# midi_thru.net
KiCad netlist of a schematic drawn in EAGLE
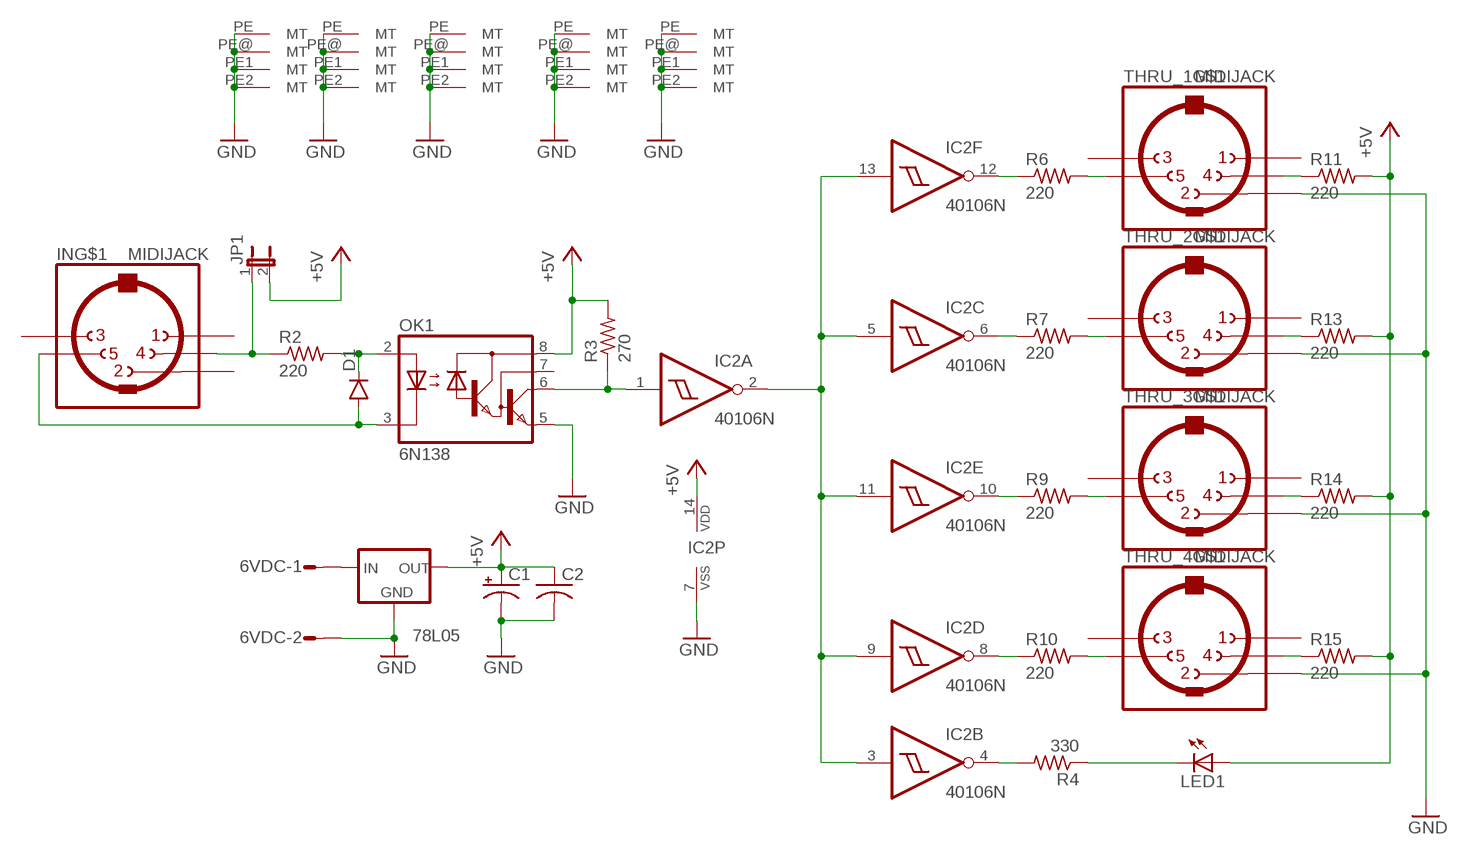
[diagram p0: schematic, sheet 1]

(export (version "E")
  (design (tool "Eeschema 10.0.6"))
  (components
    (comp (ref "6VDC")
      (value "S02P")
      (footprint "eagle-import:S02P")
      (libsource (lib "eagle-import") (part "S02P"))
    )
    (comp (ref "78L05")
      (value "79LXX")
      (footprint "eagle-import:79LXX")
      (libsource (lib "eagle-import") (part "79LXX"))
    )
    (comp (ref "C1")
      (value "CPOL-USB45181A")
      (footprint "eagle-import:B45181A")
      (libsource (lib "eagle-import") (part "CPOL-USB45181A"))
    )
    (comp (ref "C2")
      (value "C-US025-024X044")
      (footprint "eagle-import:C025-024X044")
      (libsource (lib "eagle-import") (part "C-US025-024X044"))
    )
    (comp (ref "D1")
      (value "DIODE1N4148")
      (footprint "eagle-import:DIODE-1N4148")
      (libsource (lib "eagle-import") (part "DIODE1N4148"))
    )
    (comp (ref "IC2")
      (value "40106N")
      (footprint "eagle-import:DIL14")
      (libsource (lib "eagle-import") (part "40106N"))
    )
    (comp (ref "IN")
      (value "MIDIJACK")
      (footprint "eagle-import:CP-2350")
      (libsource (lib "eagle-import") (part "MIDIJACK"))
    )
    (comp (ref "JP1")
      (value "JP1E")
      (footprint "eagle-import:JP1")
      (libsource (lib "eagle-import") (part "JP1E"))
    )
    (comp (ref "LED1")
      (value "LED5MM")
      (footprint "eagle-import:LED5MM")
      (libsource (lib "eagle-import") (part "LED5MM"))
    )
    (comp (ref "OK1")
      (value "6N138")
      (footprint "eagle-import:DIL08")
      (fields (field (name "MF") "VISHAY/TELEFUNKEN"))
      (libsource (lib "eagle-import") (part "6N138"))
    )
    (comp (ref "R2")
      (value "220")
      (footprint "eagle-import:0207_7")
      (libsource (lib "eagle-import") (part "R-US_0207/7"))
    )
    (comp (ref "R3")
      (value "270")
      (footprint "eagle-import:0207_7")
      (libsource (lib "eagle-import") (part "R-US_0207/7"))
    )
    (comp (ref "R4")
      (value "330")
      (footprint "eagle-import:0207_7")
      (libsource (lib "eagle-import") (part "R-US_0207/7"))
    )
    (comp (ref "R6")
      (value "220")
      (footprint "eagle-import:0207_7")
      (libsource (lib "eagle-import") (part "R-US_0207/7"))
    )
    (comp (ref "R7")
      (value "220")
      (footprint "eagle-import:0207_7")
      (libsource (lib "eagle-import") (part "R-US_0207/7"))
    )
    (comp (ref "R9")
      (value "220")
      (footprint "eagle-import:0207_7")
      (libsource (lib "eagle-import") (part "R-US_0207/7"))
    )
    (comp (ref "R10")
      (value "220")
      (footprint "eagle-import:0207_7")
      (libsource (lib "eagle-import") (part "R-US_0207/7"))
    )
    (comp (ref "R11")
      (value "220")
      (footprint "eagle-import:0207_7")
      (libsource (lib "eagle-import") (part "R-US_0207/7"))
    )
    (comp (ref "R13")
      (value "220")
      (footprint "eagle-import:0207_7")
      (libsource (lib "eagle-import") (part "R-US_0207/7"))
    )
    (comp (ref "R14")
      (value "220")
      (footprint "eagle-import:0207_7")
      (libsource (lib "eagle-import") (part "R-US_0207/7"))
    )
    (comp (ref "R15")
      (value "220")
      (footprint "eagle-import:0207_7")
      (libsource (lib "eagle-import") (part "R-US_0207/7"))
    )
    (comp (ref "THRU_1")
      (value "MIDIJACK")
      (footprint "eagle-import:CP-2350")
      (libsource (lib "eagle-import") (part "MIDIJACK"))
    )
    (comp (ref "THRU_2")
      (value "MIDIJACK")
      (footprint "eagle-import:CP-2350")
      (libsource (lib "eagle-import") (part "MIDIJACK"))
    )
    (comp (ref "THRU_3")
      (value "MIDIJACK")
      (footprint "eagle-import:CP-2350")
      (libsource (lib "eagle-import") (part "MIDIJACK"))
    )
    (comp (ref "THRU_4")
      (value "MIDIJACK")
      (footprint "eagle-import:CP-2350")
      (libsource (lib "eagle-import") (part "MIDIJACK"))
    )
  )
  (nets
    (net (code "1") (name "+5V") (class "Default")
      (node (ref "78L05") (pin "OUT") (pinfunction "OUT_OUT") (pintype "passive"))
      (node (ref "C1") (pin "+") (pinfunction "+_+") (pintype "passive"))
      (node (ref "C2") (pin "1") (pinfunction "1_1") (pintype "passive"))
      (node (ref "IC2") (pin "14") (pinfunction "VDD_14") (pintype "power_in"))
      (node (ref "JP1") (pin "2") (pinfunction "2_2") (pintype "passive"))
      (node (ref "LED1") (pin "A") (pinfunction "A_A") (pintype "passive"))
      (node (ref "OK1") (pin "8") (pinfunction "VCC_8") (pintype "passive"))
      (node (ref "R11") (pin "2") (pinfunction "2_2") (pintype "passive"))
      (node (ref "R13") (pin "2") (pinfunction "2_2") (pintype "passive"))
      (node (ref "R14") (pin "2") (pinfunction "2_2") (pintype "passive"))
      (node (ref "R15") (pin "2") (pinfunction "2_2") (pintype "passive"))
      (node (ref "R3") (pin "2") (pinfunction "2_2") (pintype "passive"))
    )
    (net (code "2") (name "GND") (class "Default")
      (node (ref "6VDC") (pin "2") (pinfunction "S_2") (pintype "passive"))
      (node (ref "78L05") (pin "GND") (pinfunction "GND_GND") (pintype "input"))
      (node (ref "C1") (pin "-") (pinfunction "-_-") (pintype "passive"))
      (node (ref "C2") (pin "2") (pinfunction "2_2") (pintype "passive"))
      (node (ref "IC2") (pin "7") (pinfunction "VSS_7") (pintype "power_in"))
      (node (ref "IN") (pin "PE") (pinfunction "MT_PE") (pintype "passive"))
      (node (ref "IN") (pin "PE1") (pinfunction "MT_PE1") (pintype "passive"))
      (node (ref "IN") (pin "PE2") (pinfunction "MT_PE2") (pintype "passive"))
      (node (ref "IN") (pin "PE@") (pinfunction "MT_PE@") (pintype "passive"))
      (node (ref "OK1") (pin "5") (pinfunction "GND_5") (pintype "passive"))
      (node (ref "THRU_1") (pin "2") (pinfunction "2_2") (pintype "passive"))
      (node (ref "THRU_1") (pin "PE") (pinfunction "MT_PE") (pintype "passive"))
      (node (ref "THRU_1") (pin "PE1") (pinfunction "MT_PE1") (pintype "passive"))
      (node (ref "THRU_1") (pin "PE2") (pinfunction "MT_PE2") (pintype "passive"))
      (node (ref "THRU_1") (pin "PE@") (pinfunction "MT_PE@") (pintype "passive"))
      (node (ref "THRU_2") (pin "2") (pinfunction "2_2") (pintype "passive"))
      (node (ref "THRU_2") (pin "PE") (pinfunction "MT_PE") (pintype "passive"))
      (node (ref "THRU_2") (pin "PE1") (pinfunction "MT_PE1") (pintype "passive"))
      (node (ref "THRU_2") (pin "PE2") (pinfunction "MT_PE2") (pintype "passive"))
      (node (ref "THRU_2") (pin "PE@") (pinfunction "MT_PE@") (pintype "passive"))
      (node (ref "THRU_3") (pin "2") (pinfunction "2_2") (pintype "passive"))
      (node (ref "THRU_3") (pin "PE") (pinfunction "MT_PE") (pintype "passive"))
      (node (ref "THRU_3") (pin "PE1") (pinfunction "MT_PE1") (pintype "passive"))
      (node (ref "THRU_3") (pin "PE2") (pinfunction "MT_PE2") (pintype "passive"))
      (node (ref "THRU_3") (pin "PE@") (pinfunction "MT_PE@") (pintype "passive"))
      (node (ref "THRU_4") (pin "2") (pinfunction "2_2") (pintype "passive"))
      (node (ref "THRU_4") (pin "PE") (pinfunction "MT_PE") (pintype "passive"))
      (node (ref "THRU_4") (pin "PE1") (pinfunction "MT_PE1") (pintype "passive"))
      (node (ref "THRU_4") (pin "PE2") (pinfunction "MT_PE2") (pintype "passive"))
      (node (ref "THRU_4") (pin "PE@") (pinfunction "MT_PE@") (pintype "passive"))
    )
    (net (code "3") (name "Net-(6VDCA-S)") (class "Default")
      (node (ref "6VDC") (pin "1") (pinfunction "S_1") (pintype "passive"))
      (node (ref "78L05") (pin "IN") (pinfunction "IN_IN") (pintype "input"))
    )
    (net (code "4") (name "Net-(IC2A-I)") (class "Default")
      (node (ref "IC2") (pin "1") (pinfunction "I_1") (pintype "input"))
      (node (ref "OK1") (pin "6") (pinfunction "VO_6") (pintype "passive"))
      (node (ref "R3") (pin "1") (pinfunction "1_1") (pintype "passive"))
    )
    (net (code "5") (name "Net-(IC2A-O)") (class "Default")
      (node (ref "IC2") (pin "11") (pinfunction "I_11") (pintype "input"))
      (node (ref "IC2") (pin "13") (pinfunction "I_13") (pintype "input"))
      (node (ref "IC2") (pin "2") (pinfunction "O_2") (pintype "output"))
      (node (ref "IC2") (pin "3") (pinfunction "I_3") (pintype "input"))
      (node (ref "IC2") (pin "5") (pinfunction "I_5") (pintype "input"))
      (node (ref "IC2") (pin "9") (pinfunction "I_9") (pintype "input"))
    )
    (net (code "6") (name "Net-(IC2B-O)") (class "Default")
      (node (ref "IC2") (pin "4") (pinfunction "O_4") (pintype "output"))
      (node (ref "R4") (pin "2") (pinfunction "2_2") (pintype "passive"))
    )
    (net (code "7") (name "Net-(IC2C-O)") (class "Default")
      (node (ref "IC2") (pin "6") (pinfunction "O_6") (pintype "output"))
      (node (ref "R7") (pin "1") (pinfunction "1_1") (pintype "passive"))
    )
    (net (code "8") (name "Net-(IC2D-O)") (class "Default")
      (node (ref "IC2") (pin "8") (pinfunction "O_8") (pintype "output"))
      (node (ref "R10") (pin "1") (pinfunction "1_1") (pintype "passive"))
    )
    (net (code "9") (name "Net-(IC2E-O)") (class "Default")
      (node (ref "IC2") (pin "10") (pinfunction "O_10") (pintype "output"))
      (node (ref "R9") (pin "1") (pinfunction "1_1") (pintype "passive"))
    )
    (net (code "10") (name "Net-(IC2F-O)") (class "Default")
      (node (ref "IC2") (pin "12") (pinfunction "O_12") (pintype "output"))
      (node (ref "R6") (pin "1") (pinfunction "1_1") (pintype "passive"))
    )
    (net (code "11") (name "Net-(IN-Pad4)") (class "Default")
      (node (ref "IN") (pin "4") (pinfunction "4_4") (pintype "passive"))
      (node (ref "JP1") (pin "1") (pinfunction "1_1") (pintype "passive"))
      (node (ref "R2") (pin "1") (pinfunction "1_1") (pintype "passive"))
    )
    (net (code "12") (name "Net-(LED1-C)") (class "Default")
      (node (ref "LED1") (pin "K") (pinfunction "C_K") (pintype "passive"))
      (node (ref "R4") (pin "1") (pinfunction "1_1") (pintype "passive"))
    )
    (net (code "13") (name "Net-(OK1-A)") (class "Default")
      (node (ref "D1") (pin "C") (pinfunction "C_C") (pintype "passive"))
      (node (ref "OK1") (pin "2") (pinfunction "A_2") (pintype "passive"))
      (node (ref "R2") (pin "2") (pinfunction "2_2") (pintype "passive"))
    )
    (net (code "14") (name "Net-(OK1-C)") (class "Default")
      (node (ref "D1") (pin "A") (pinfunction "A_A") (pintype "passive"))
      (node (ref "IN") (pin "5") (pinfunction "5_5") (pintype "passive"))
      (node (ref "OK1") (pin "3") (pinfunction "C_3") (pintype "passive"))
    )
    (net (code "15") (name "Net-(R6-Pad2)") (class "Default")
      (node (ref "R6") (pin "2") (pinfunction "2_2") (pintype "passive"))
      (node (ref "THRU_1") (pin "5") (pinfunction "5_5") (pintype "passive"))
    )
    (net (code "16") (name "Net-(R7-Pad2)") (class "Default")
      (node (ref "R7") (pin "2") (pinfunction "2_2") (pintype "passive"))
      (node (ref "THRU_2") (pin "5") (pinfunction "5_5") (pintype "passive"))
    )
    (net (code "17") (name "Net-(R9-Pad2)") (class "Default")
      (node (ref "R9") (pin "2") (pinfunction "2_2") (pintype "passive"))
      (node (ref "THRU_3") (pin "5") (pinfunction "5_5") (pintype "passive"))
    )
    (net (code "18") (name "Net-(R10-Pad2)") (class "Default")
      (node (ref "R10") (pin "2") (pinfunction "2_2") (pintype "passive"))
      (node (ref "THRU_4") (pin "5") (pinfunction "5_5") (pintype "passive"))
    )
    (net (code "19") (name "Net-(R11-Pad1)") (class "Default")
      (node (ref "R11") (pin "1") (pinfunction "1_1") (pintype "passive"))
      (node (ref "THRU_1") (pin "4") (pinfunction "4_4") (pintype "passive"))
    )
    (net (code "20") (name "Net-(R13-Pad1)") (class "Default")
      (node (ref "R13") (pin "1") (pinfunction "1_1") (pintype "passive"))
      (node (ref "THRU_2") (pin "4") (pinfunction "4_4") (pintype "passive"))
    )
    (net (code "21") (name "Net-(R14-Pad1)") (class "Default")
      (node (ref "R14") (pin "1") (pinfunction "1_1") (pintype "passive"))
      (node (ref "THRU_3") (pin "4") (pinfunction "4_4") (pintype "passive"))
    )
    (net (code "22") (name "Net-(R15-Pad1)") (class "Default")
      (node (ref "R15") (pin "1") (pinfunction "1_1") (pintype "passive"))
      (node (ref "THRU_4") (pin "4") (pinfunction "4_4") (pintype "passive"))
    )
    (net (code "23") (name "unconnected-(IN-Pad1)") (class "Default")
      (node (ref "IN") (pin "1") (pinfunction "1_1") (pintype "passive"))
    )
    (net (code "24") (name "unconnected-(IN-Pad2)") (class "Default")
      (node (ref "IN") (pin "2") (pinfunction "2_2") (pintype "passive"))
    )
    (net (code "25") (name "unconnected-(IN-Pad3)") (class "Default")
      (node (ref "IN") (pin "3") (pinfunction "3_3") (pintype "passive"))
    )
    (net (code "26") (name "unconnected-(OK1-VB-Pad7)") (class "Default")
      (node (ref "OK1") (pin "7") (pinfunction "VB_7") (pintype "passive"))
    )
    (net (code "27") (name "unconnected-(THRU_1-Pad1)") (class "Default")
      (node (ref "THRU_1") (pin "1") (pinfunction "1_1") (pintype "passive"))
    )
    (net (code "28") (name "unconnected-(THRU_1-Pad3)") (class "Default")
      (node (ref "THRU_1") (pin "3") (pinfunction "3_3") (pintype "passive"))
    )
    (net (code "29") (name "unconnected-(THRU_2-Pad1)") (class "Default")
      (node (ref "THRU_2") (pin "1") (pinfunction "1_1") (pintype "passive"))
    )
    (net (code "30") (name "unconnected-(THRU_2-Pad3)") (class "Default")
      (node (ref "THRU_2") (pin "3") (pinfunction "3_3") (pintype "passive"))
    )
    (net (code "31") (name "unconnected-(THRU_3-Pad1)") (class "Default")
      (node (ref "THRU_3") (pin "1") (pinfunction "1_1") (pintype "passive"))
    )
    (net (code "32") (name "unconnected-(THRU_3-Pad3)") (class "Default")
      (node (ref "THRU_3") (pin "3") (pinfunction "3_3") (pintype "passive"))
    )
    (net (code "33") (name "unconnected-(THRU_4-Pad1)") (class "Default")
      (node (ref "THRU_4") (pin "1") (pinfunction "1_1") (pintype "passive"))
    )
    (net (code "34") (name "unconnected-(THRU_4-Pad3)") (class "Default")
      (node (ref "THRU_4") (pin "3") (pinfunction "3_3") (pintype "passive"))
    )
  )
)
